# ChristmasOrnament.net
KiCad netlist of a schematic drawn in EAGLE
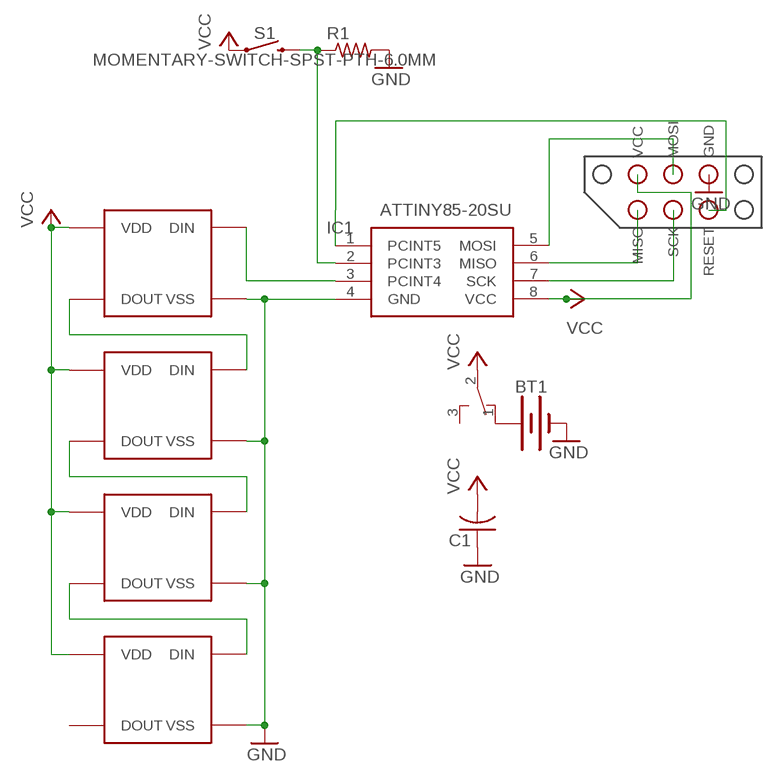
[diagram p0: schematic, sheet 1]

(export (version "E")
  (design (tool "Eeschema 10.0.6"))
  (components
    (comp (ref "BT1")
      (value "BATTERY-20MM_SMD_4LEGS_OVERPASTE")
      (footprint "eagle-import:BATTCON_20MM_4LEGS_OVERPASTE")
      (libsource (lib "eagle-import") (part "BATTERY-20MM_SMD_4LEGS_OVERPASTE"))
    )
    (comp (ref "C1")
      (value "C-USC0402")
      (footprint "eagle-import:C0402")
      (libsource (lib "eagle-import") (part "C-USC0402"))
    )
    (comp (ref "IC1")
      (value "ATTINY85-20SU")
      (footprint "eagle-import:SOT127P798X216-8N")
      (fields (field (name "MOUSER_PART_NUMBER") "556-ATTINY85-20SU"))
      (libsource (lib "eagle-import") (part "ATTINY85-20SU"))
    )
    (comp (ref "R1")
      (value "R-US_R0402")
      (footprint "eagle-import:R0402")
      (libsource (lib "eagle-import") (part "R-US_R0402"))
    )
    (comp (ref "S1")
      (value "MOMENTARY-SWITCH-SPST-PTH-6.0MM")
      (footprint "eagle-import:TACTILE_SWITCH_PTH_6.0MM")
      (libsource (lib "eagle-import") (part "MOMENTARY-SWITCH-SPST-PTH-6.0MM"))
    )
    (comp (ref "U$1")
      (value "SK6812")
      (footprint "eagle-import:OSCL320P500X500X160-4N")
      (libsource (lib "eagle-import") (part "SK6812"))
    )
    (comp (ref "U$2")
      (value "SK6812")
      (footprint "eagle-import:OSCL320P500X500X160-4N")
      (libsource (lib "eagle-import") (part "SK6812"))
    )
    (comp (ref "U$3")
      (value "SK6812")
      (footprint "eagle-import:OSCL320P500X500X160-4N")
      (libsource (lib "eagle-import") (part "SK6812"))
    )
    (comp (ref "U$4")
      (value "SK6812")
      (footprint "eagle-import:OSCL320P500X500X160-4N")
      (libsource (lib "eagle-import") (part "SK6812"))
    )
    (comp (ref "U$5")
      (value "PROGRAMMING-PORT")
      (footprint "eagle-import:PROGRAMMING-PORT")
      (libsource (lib "eagle-import") (part "PROGRAMMING-PORT"))
    )
    (comp (ref "U$6")
      (value "SLIDE-SWITCH")
      (footprint "eagle-import:SLIDE-SWITCH")
      (libsource (lib "eagle-import") (part "SLIDE-SWITCH"))
    )
  )
  (nets
    (net (code "1") (name "GND") (class "Default")
      (node (ref "BT1") (pin "2") (pinfunction "-_2") (pintype "power_in"))
      (node (ref "C1") (pin "1") (pinfunction "1_1") (pintype "passive"))
      (node (ref "IC1") (pin "4") (pinfunction "GND_4") (pintype "power_in"))
      (node (ref "R1") (pin "2") (pinfunction "2_2") (pintype "passive"))
      (node (ref "U$1") (pin "3") (pinfunction "VSS_3") (pintype "bidirectional"))
      (node (ref "U$2") (pin "3") (pinfunction "VSS_3") (pintype "bidirectional"))
      (node (ref "U$3") (pin "3") (pinfunction "VSS_3") (pintype "bidirectional"))
      (node (ref "U$4") (pin "3") (pinfunction "VSS_3") (pintype "bidirectional"))
      (node (ref "U$5") (pin "P$6") (pinfunction "GND_P$6") (pintype "bidirectional"))
    )
    (net (code "2") (name "Net-(BT1-+)") (class "Default")
      (node (ref "BT1") (pin "1") (pinfunction "+_1") (pintype "power_in"))
      (node (ref "U$6") (pin "1") (pinfunction "P$1_1") (pintype "bidirectional"))
    )
    (net (code "3") (name "Net-(IC1-MISO)") (class "Default")
      (node (ref "IC1") (pin "6") (pinfunction "MISO_6") (pintype "bidirectional"))
      (node (ref "U$5") (pin "P$1") (pinfunction "MISO_P$1") (pintype "bidirectional"))
    )
    (net (code "4") (name "Net-(IC1-MOSI)") (class "Default")
      (node (ref "IC1") (pin "5") (pinfunction "MOSI_5") (pintype "bidirectional"))
      (node (ref "U$5") (pin "P$4") (pinfunction "MOSI_P$4") (pintype "bidirectional"))
    )
    (net (code "5") (name "Net-(IC1-PCINT3)") (class "Default")
      (node (ref "IC1") (pin "2") (pinfunction "PCINT3_2") (pintype "bidirectional"))
      (node (ref "R1") (pin "1") (pinfunction "1_1") (pintype "passive"))
      (node (ref "S1") (pin "3") (pinfunction "2_3") (pintype "passive"))
    )
    (net (code "6") (name "Net-(IC1-PCINT4)") (class "Default")
      (node (ref "IC1") (pin "3") (pinfunction "PCINT4_3") (pintype "bidirectional"))
      (node (ref "U$1") (pin "4") (pinfunction "DIN_4") (pintype "bidirectional"))
    )
    (net (code "7") (name "Net-(IC1-PCINT5)") (class "Default")
      (node (ref "IC1") (pin "1") (pinfunction "PCINT5_1") (pintype "bidirectional"))
      (node (ref "U$5") (pin "P$5") (pinfunction "RESET_P$5") (pintype "bidirectional"))
    )
    (net (code "8") (name "Net-(IC1-SCK)") (class "Default")
      (node (ref "IC1") (pin "7") (pinfunction "SCK_7") (pintype "bidirectional"))
      (node (ref "U$5") (pin "P$3") (pinfunction "SCK_P$3") (pintype "bidirectional"))
    )
    (net (code "9") (name "Net-(U$1-DOUT)") (class "Default")
      (node (ref "U$1") (pin "2") (pinfunction "DOUT_2") (pintype "bidirectional"))
      (node (ref "U$2") (pin "4") (pinfunction "DIN_4") (pintype "bidirectional"))
    )
    (net (code "10") (name "Net-(U$2-DOUT)") (class "Default")
      (node (ref "U$2") (pin "2") (pinfunction "DOUT_2") (pintype "bidirectional"))
      (node (ref "U$3") (pin "4") (pinfunction "DIN_4") (pintype "bidirectional"))
    )
    (net (code "11") (name "Net-(U$3-DOUT)") (class "Default")
      (node (ref "U$3") (pin "2") (pinfunction "DOUT_2") (pintype "bidirectional"))
      (node (ref "U$4") (pin "4") (pinfunction "DIN_4") (pintype "bidirectional"))
    )
    (net (code "12") (name "VCC") (class "Default")
      (node (ref "C1") (pin "2") (pinfunction "2_2") (pintype "passive"))
      (node (ref "IC1") (pin "8") (pinfunction "VCC_8") (pintype "power_in"))
      (node (ref "S1") (pin "1") (pinfunction "1_1") (pintype "passive"))
      (node (ref "U$1") (pin "1") (pinfunction "VDD_1") (pintype "bidirectional"))
      (node (ref "U$2") (pin "1") (pinfunction "VDD_1") (pintype "bidirectional"))
      (node (ref "U$3") (pin "1") (pinfunction "VDD_1") (pintype "bidirectional"))
      (node (ref "U$4") (pin "1") (pinfunction "VDD_1") (pintype "bidirectional"))
      (node (ref "U$5") (pin "P$2") (pinfunction "VCC_P$2") (pintype "bidirectional"))
      (node (ref "U$6") (pin "2") (pinfunction "P$2_2") (pintype "bidirectional"))
    )
    (net (code "13") (name "unconnected-(U$4-DOUT-Pad2)") (class "Default")
      (node (ref "U$4") (pin "2") (pinfunction "DOUT_2") (pintype "bidirectional"))
    )
    (net (code "14") (name "unconnected-(U$6-P$3-Pad3)") (class "Default")
      (node (ref "U$6") (pin "3") (pinfunction "P$3_3") (pintype "bidirectional"))
    )
  )
)
